# SAM3U_Breakout.net
KiCad netlist of a schematic drawn in EAGLE
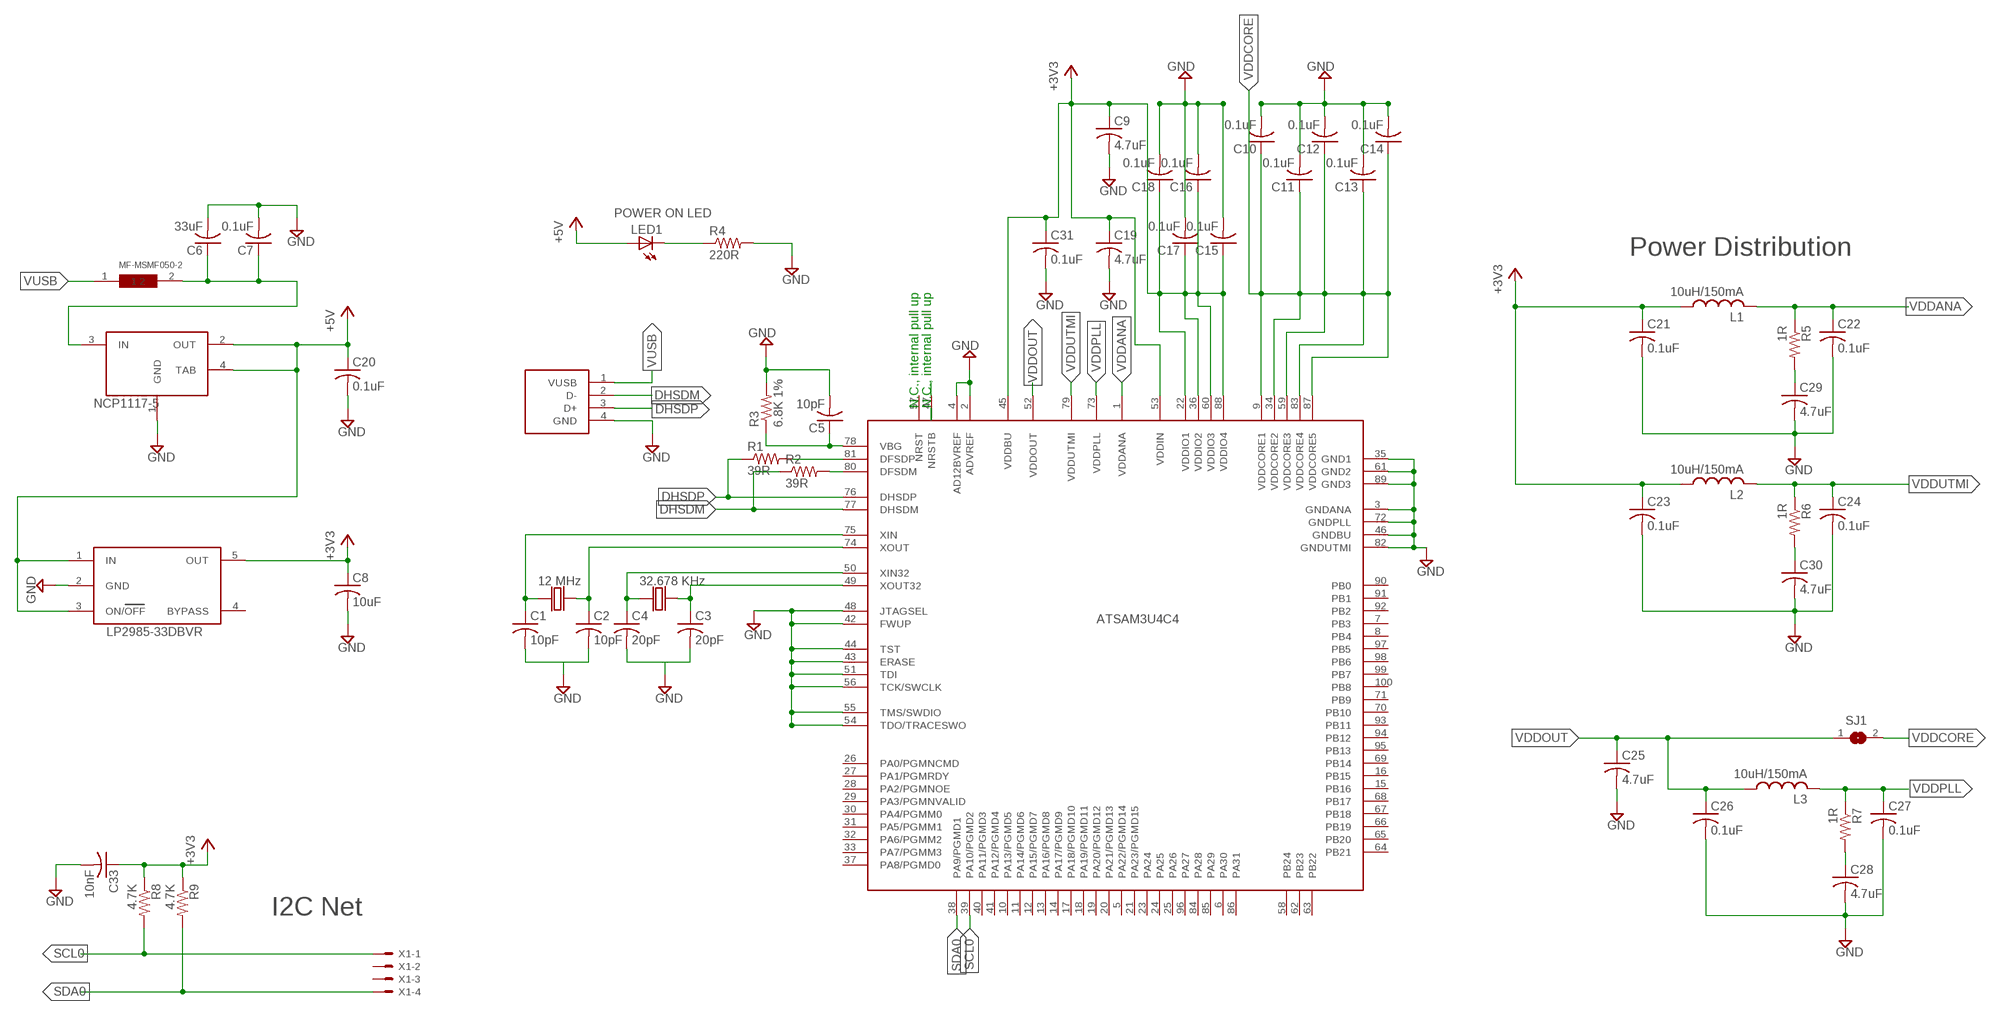
[diagram p0: schematic, sheet 1]

(export (version "E")
  (design (tool "Eeschema 10.0.6"))
  (components
    (comp (ref "C1")
      (value "10pF")
      (footprint "eagle-import:C0402K")
      (libsource (lib "eagle-import") (part "C-USC0402K"))
    )
    (comp (ref "C2")
      (value "10pF")
      (footprint "eagle-import:C0402K")
      (libsource (lib "eagle-import") (part "C-USC0402K"))
    )
    (comp (ref "C3")
      (value "20pF")
      (footprint "eagle-import:C0402K")
      (libsource (lib "eagle-import") (part "C-USC0402K"))
    )
    (comp (ref "C4")
      (value "20pF")
      (footprint "eagle-import:C0402K")
      (libsource (lib "eagle-import") (part "C-USC0402K"))
    )
    (comp (ref "C5")
      (value "10pF")
      (footprint "eagle-import:C0402K")
      (libsource (lib "eagle-import") (part "C-USC0402K"))
    )
    (comp (ref "C6")
      (value "33uF")
      (footprint "eagle-import:C0402K")
      (libsource (lib "eagle-import") (part "C-USC0402K"))
    )
    (comp (ref "C7")
      (value "0.1uF")
      (footprint "eagle-import:C0402K")
      (libsource (lib "eagle-import") (part "C-USC0402K"))
    )
    (comp (ref "C8")
      (value "10uF")
      (footprint "eagle-import:C0402K")
      (libsource (lib "eagle-import") (part "C-USC0402K"))
    )
    (comp (ref "C9")
      (value "4.7uF")
      (footprint "eagle-import:C0402K")
      (libsource (lib "eagle-import") (part "C-USC0402K"))
    )
    (comp (ref "C10")
      (value "0.1uF")
      (footprint "eagle-import:C0402K")
      (libsource (lib "eagle-import") (part "C-USC0402K"))
    )
    (comp (ref "C11")
      (value "0.1uF")
      (footprint "eagle-import:C0402K")
      (libsource (lib "eagle-import") (part "C-USC0402K"))
    )
    (comp (ref "C12")
      (value "0.1uF")
      (footprint "eagle-import:C0402K")
      (libsource (lib "eagle-import") (part "C-USC0402K"))
    )
    (comp (ref "C13")
      (value "0.1uF")
      (footprint "eagle-import:C0402K")
      (libsource (lib "eagle-import") (part "C-USC0402K"))
    )
    (comp (ref "C14")
      (value "0.1uF")
      (footprint "eagle-import:C0402K")
      (libsource (lib "eagle-import") (part "C-USC0402K"))
    )
    (comp (ref "C15")
      (value "0.1uF")
      (footprint "eagle-import:C0402K")
      (libsource (lib "eagle-import") (part "C-USC0402K"))
    )
    (comp (ref "C16")
      (value "0.1uF")
      (footprint "eagle-import:C0402K")
      (libsource (lib "eagle-import") (part "C-USC0402K"))
    )
    (comp (ref "C17")
      (value "0.1uF")
      (footprint "eagle-import:C0402K")
      (libsource (lib "eagle-import") (part "C-USC0402K"))
    )
    (comp (ref "C18")
      (value "0.1uF")
      (footprint "eagle-import:C0402K")
      (libsource (lib "eagle-import") (part "C-USC0402K"))
    )
    (comp (ref "C19")
      (value "4.7uF")
      (footprint "eagle-import:C0402K")
      (libsource (lib "eagle-import") (part "C-USC0402K"))
    )
    (comp (ref "C20")
      (value "0.1uF")
      (footprint "eagle-import:C0402K")
      (libsource (lib "eagle-import") (part "C-USC0402K"))
    )
    (comp (ref "C21")
      (value "0.1uF")
      (footprint "eagle-import:C0402K")
      (libsource (lib "eagle-import") (part "C-USC0402K"))
    )
    (comp (ref "C22")
      (value "0.1uF")
      (footprint "eagle-import:C0402K")
      (libsource (lib "eagle-import") (part "C-USC0402K"))
    )
    (comp (ref "C23")
      (value "0.1uF")
      (footprint "eagle-import:C0402K")
      (libsource (lib "eagle-import") (part "C-USC0402K"))
    )
    (comp (ref "C24")
      (value "0.1uF")
      (footprint "eagle-import:C0402K")
      (libsource (lib "eagle-import") (part "C-USC0402K"))
    )
    (comp (ref "C25")
      (value "4.7uF")
      (footprint "eagle-import:C0402K")
      (libsource (lib "eagle-import") (part "C-USC0402K"))
    )
    (comp (ref "C26")
      (value "0.1uF")
      (footprint "eagle-import:C0402K")
      (libsource (lib "eagle-import") (part "C-USC0402K"))
    )
    (comp (ref "C27")
      (value "0.1uF")
      (footprint "eagle-import:C0402K")
      (libsource (lib "eagle-import") (part "C-USC0402K"))
    )
    (comp (ref "C28")
      (value "4.7uF")
      (footprint "eagle-import:C0402K")
      (libsource (lib "eagle-import") (part "C-USC0402K"))
    )
    (comp (ref "C29")
      (value "4.7uF")
      (footprint "eagle-import:C0402K")
      (libsource (lib "eagle-import") (part "C-USC0402K"))
    )
    (comp (ref "C30")
      (value "4.7uF")
      (footprint "eagle-import:C0402K")
      (libsource (lib "eagle-import") (part "C-USC0402K"))
    )
    (comp (ref "C31")
      (value "0.1uF")
      (footprint "eagle-import:C0402K")
      (libsource (lib "eagle-import") (part "C-USC0402K"))
    )
    (comp (ref "C33")
      (value "10nF")
      (footprint "eagle-import:C0402K")
      (libsource (lib "eagle-import") (part "C-USC0402K"))
    )
    (comp (ref "L1")
      (value "10uH/150mA")
      (footprint "eagle-import:L2012C")
      (libsource (lib "eagle-import") (part "L-USL2012C"))
    )
    (comp (ref "L2")
      (value "10uH/150mA")
      (footprint "eagle-import:L2012C")
      (libsource (lib "eagle-import") (part "L-USL2012C"))
    )
    (comp (ref "L3")
      (value "10uH/150mA")
      (footprint "eagle-import:L2012C")
      (libsource (lib "eagle-import") (part "L-USL2012C"))
    )
    (comp (ref "LED1")
      (value "LEDCHIP-LED0603")
      (footprint "eagle-import:CHIP-LED0603")
      (libsource (lib "eagle-import") (part "LEDCHIP-LED0603"))
    )
    (comp (ref "R1")
      (value "39R")
      (footprint "eagle-import:R0402")
      (libsource (lib "eagle-import") (part "R-US_R0402"))
    )
    (comp (ref "R2")
      (value "39R")
      (footprint "eagle-import:R0402")
      (libsource (lib "eagle-import") (part "R-US_R0402"))
    )
    (comp (ref "R3")
      (value "6.8K 1%")
      (footprint "eagle-import:R0402")
      (libsource (lib "eagle-import") (part "resistor_R-US_R0402"))
    )
    (comp (ref "R4")
      (value "220R")
      (footprint "eagle-import:R0402")
      (libsource (lib "eagle-import") (part "R-US_R0402"))
    )
    (comp (ref "R5")
      (value "1R")
      (footprint "eagle-import:R0402")
      (libsource (lib "eagle-import") (part "resistor_R-US_R0402"))
    )
    (comp (ref "R6")
      (value "1R")
      (footprint "eagle-import:R0402")
      (libsource (lib "eagle-import") (part "resistor_R-US_R0402"))
    )
    (comp (ref "R7")
      (value "1R")
      (footprint "eagle-import:R0402")
      (libsource (lib "eagle-import") (part "resistor_R-US_R0402"))
    )
    (comp (ref "R8")
      (value "4.7K")
      (footprint "eagle-import:R0402")
      (libsource (lib "eagle-import") (part "R-US_R0402"))
    )
    (comp (ref "R9")
      (value "4.7K")
      (footprint "eagle-import:R0402")
      (libsource (lib "eagle-import") (part "R-US_R0402"))
    )
    (comp (ref "SJ1") (value "SJ") (footprint "eagle-import:SJ") (libsource (lib "eagle-import") (part "SJ")))
    (comp (ref "U$1")
      (value "ATSAM3UC4-PA")
      (footprint "eagle-import:QFP50P1600X1600X160-100N")
      (libsource (lib "eagle-import") (part "ATSAM3UC4-PA"))
    )
    (comp (ref "U$2")
      (value "USB_TYPE_A_KEYSTN")
      (footprint "eagle-import:USB_TYPE_PLUG_KSTN_PACK")
      (libsource (lib "eagle-import") (part "USB_TYPE_A_KEYSTN"))
    )
    (comp (ref "U$3")
      (value "AVX_CRYSTAL_12MHZ")
      (footprint "eagle-import:AVX_CRYSTAL_12MHZ_PACK")
      (libsource (lib "eagle-import") (part "AVX_CRYSTAL_12MHZ"))
    )
    (comp (ref "U$4")
      (value "AVX_ST43_CRYSTAL_32768")
      (footprint "eagle-import:AVX_ST32_CRYSTAL_32768_PACK")
      (libsource (lib "eagle-import") (part "AVX_ST43_CRYSTAL_32768"))
    )
    (comp (ref "U$5")
      (value "NCP1117-55V")
      (footprint "eagle-import:NCP1117-5-SOT")
      (libsource (lib "eagle-import") (part "NCP1117-55V"))
    )
    (comp (ref "U$6")
      (value "MF-MSMF050-2")
      (footprint "eagle-import:MF-MSMF050-PACK")
      (libsource (lib "eagle-import") (part "MF-MSMF050-2"))
    )
    (comp (ref "U$7")
      (value "LP2985-33DBVR5-PIN")
      (footprint "eagle-import:LP2985-33DBVR-SO")
      (libsource (lib "eagle-import") (part "LP2985-33DBVR5-PIN"))
    )
    (comp (ref "X1")
      (value "KK-156-4")
      (footprint "eagle-import:KK-156-4")
      (libsource (lib "eagle-import") (part "KK-156-4"))
    )
  )
  (nets
    (net (code "1") (name "+3V3") (class "Default")
      (node (ref "C15") (pin "1") (pinfunction "1_1") (pintype "passive"))
      (node (ref "C16") (pin "1") (pinfunction "1_1") (pintype "passive"))
      (node (ref "C17") (pin "1") (pinfunction "1_1") (pintype "passive"))
      (node (ref "C18") (pin "1") (pinfunction "1_1") (pintype "passive"))
      (node (ref "C19") (pin "1") (pinfunction "1_1") (pintype "passive"))
      (node (ref "C21") (pin "1") (pinfunction "1_1") (pintype "passive"))
      (node (ref "C23") (pin "1") (pinfunction "1_1") (pintype "passive"))
      (node (ref "C31") (pin "1") (pinfunction "1_1") (pintype "passive"))
      (node (ref "C33") (pin "1") (pinfunction "1_1") (pintype "passive"))
      (node (ref "C8") (pin "1") (pinfunction "1_1") (pintype "passive"))
      (node (ref "C9") (pin "1") (pinfunction "1_1") (pintype "passive"))
      (node (ref "L1") (pin "1") (pinfunction "1_1") (pintype "passive"))
      (node (ref "L2") (pin "1") (pinfunction "1_1") (pintype "passive"))
      (node (ref "R8") (pin "1") (pinfunction "1_1") (pintype "passive"))
      (node (ref "R9") (pin "1") (pinfunction "1_1") (pintype "passive"))
      (node (ref "U$1") (pin "22") (pinfunction "VDDIO1_22") (pintype "bidirectional"))
      (node (ref "U$1") (pin "36") (pinfunction "VDDIO2_36") (pintype "bidirectional"))
      (node (ref "U$1") (pin "45") (pinfunction "VDDBU_45") (pintype "bidirectional"))
      (node (ref "U$1") (pin "53") (pinfunction "VDDIN_53") (pintype "bidirectional"))
      (node (ref "U$1") (pin "60") (pinfunction "VDDIO3_60") (pintype "bidirectional"))
      (node (ref "U$1") (pin "88") (pinfunction "VDDIO4_88") (pintype "bidirectional"))
      (node (ref "U$7") (pin "5") (pinfunction "OUT_5") (pintype "bidirectional"))
    )
    (net (code "2") (name "+5V") (class "Default")
      (node (ref "C20") (pin "1") (pinfunction "1_1") (pintype "passive"))
      (node (ref "LED1") (pin "A") (pinfunction "A_A") (pintype "passive"))
      (node (ref "U$5") (pin "2") (pinfunction "OUT_2") (pintype "bidirectional"))
      (node (ref "U$5") (pin "4") (pinfunction "TAB_4") (pintype "bidirectional"))
      (node (ref "U$7") (pin "1") (pinfunction "IN_1") (pintype "bidirectional"))
      (node (ref "U$7") (pin "3") (pinfunction "ON/OFF_3") (pintype "bidirectional"))
    )
    (net (code "3") (name "DHSDM") (class "Default")
      (node (ref "R2") (pin "1") (pinfunction "1_1") (pintype "passive"))
      (node (ref "U$1") (pin "77") (pinfunction "DHSDM_77") (pintype "bidirectional"))
      (node (ref "U$2") (pin "2") (pinfunction "D-_2") (pintype "bidirectional"))
    )
    (net (code "4") (name "DHSDP") (class "Default")
      (node (ref "R1") (pin "1") (pinfunction "1_1") (pintype "passive"))
      (node (ref "U$1") (pin "76") (pinfunction "DHSDP_76") (pintype "bidirectional"))
      (node (ref "U$2") (pin "3") (pinfunction "D+_3") (pintype "bidirectional"))
    )
    (net (code "5") (name "GND") (class "Default")
      (node (ref "C1") (pin "2") (pinfunction "2_2") (pintype "passive"))
      (node (ref "C10") (pin "2") (pinfunction "2_2") (pintype "passive"))
      (node (ref "C11") (pin "2") (pinfunction "2_2") (pintype "passive"))
      (node (ref "C12") (pin "2") (pinfunction "2_2") (pintype "passive"))
      (node (ref "C13") (pin "2") (pinfunction "2_2") (pintype "passive"))
      (node (ref "C14") (pin "2") (pinfunction "2_2") (pintype "passive"))
      (node (ref "C15") (pin "2") (pinfunction "2_2") (pintype "passive"))
      (node (ref "C16") (pin "2") (pinfunction "2_2") (pintype "passive"))
      (node (ref "C17") (pin "2") (pinfunction "2_2") (pintype "passive"))
      (node (ref "C18") (pin "2") (pinfunction "2_2") (pintype "passive"))
      (node (ref "C19") (pin "2") (pinfunction "2_2") (pintype "passive"))
      (node (ref "C2") (pin "2") (pinfunction "2_2") (pintype "passive"))
      (node (ref "C20") (pin "2") (pinfunction "2_2") (pintype "passive"))
      (node (ref "C21") (pin "2") (pinfunction "2_2") (pintype "passive"))
      (node (ref "C22") (pin "2") (pinfunction "2_2") (pintype "passive"))
      (node (ref "C23") (pin "2") (pinfunction "2_2") (pintype "passive"))
      (node (ref "C24") (pin "2") (pinfunction "2_2") (pintype "passive"))
      (node (ref "C25") (pin "2") (pinfunction "2_2") (pintype "passive"))
      (node (ref "C26") (pin "2") (pinfunction "2_2") (pintype "passive"))
      (node (ref "C27") (pin "2") (pinfunction "2_2") (pintype "passive"))
      (node (ref "C28") (pin "2") (pinfunction "2_2") (pintype "passive"))
      (node (ref "C29") (pin "2") (pinfunction "2_2") (pintype "passive"))
      (node (ref "C3") (pin "2") (pinfunction "2_2") (pintype "passive"))
      (node (ref "C30") (pin "2") (pinfunction "2_2") (pintype "passive"))
      (node (ref "C31") (pin "2") (pinfunction "2_2") (pintype "passive"))
      (node (ref "C33") (pin "2") (pinfunction "2_2") (pintype "passive"))
      (node (ref "C4") (pin "2") (pinfunction "2_2") (pintype "passive"))
      (node (ref "C5") (pin "2") (pinfunction "2_2") (pintype "passive"))
      (node (ref "C6") (pin "2") (pinfunction "2_2") (pintype "passive"))
      (node (ref "C7") (pin "2") (pinfunction "2_2") (pintype "passive"))
      (node (ref "C8") (pin "2") (pinfunction "2_2") (pintype "passive"))
      (node (ref "C9") (pin "2") (pinfunction "2_2") (pintype "passive"))
      (node (ref "R3") (pin "2") (pinfunction "2_2") (pintype "passive"))
      (node (ref "R4") (pin "2") (pinfunction "2_2") (pintype "passive"))
      (node (ref "U$1") (pin "2") (pinfunction "ADVREF_2") (pintype "bidirectional"))
      (node (ref "U$1") (pin "3") (pinfunction "GNDANA_3") (pintype "bidirectional"))
      (node (ref "U$1") (pin "35") (pinfunction "GND1_35") (pintype "bidirectional"))
      (node (ref "U$1") (pin "4") (pinfunction "AD12BVREF_4") (pintype "bidirectional"))
      (node (ref "U$1") (pin "42") (pinfunction "FWUP_42") (pintype "bidirectional"))
      (node (ref "U$1") (pin "43") (pinfunction "ERASE_43") (pintype "bidirectional"))
      (node (ref "U$1") (pin "44") (pinfunction "TST_44") (pintype "bidirectional"))
      (node (ref "U$1") (pin "46") (pinfunction "GNDBU_46") (pintype "bidirectional"))
      (node (ref "U$1") (pin "48") (pinfunction "JTAGSEL_48") (pintype "bidirectional"))
      (node (ref "U$1") (pin "51") (pinfunction "TDI_51") (pintype "bidirectional"))
      (node (ref "U$1") (pin "54") (pinfunction "TDO/TRACESWO_54") (pintype "bidirectional"))
      (node (ref "U$1") (pin "55") (pinfunction "TMS/SWDIO_55") (pintype "bidirectional"))
      (node (ref "U$1") (pin "56") (pinfunction "TCK/SWCLK_56") (pintype "bidirectional"))
      (node (ref "U$1") (pin "61") (pinfunction "GND2_61") (pintype "bidirectional"))
      (node (ref "U$1") (pin "72") (pinfunction "GNDPLL_72") (pintype "bidirectional"))
      (node (ref "U$1") (pin "82") (pinfunction "GNDUTMI_82") (pintype "bidirectional"))
      (node (ref "U$1") (pin "89") (pinfunction "GND3_89") (pintype "bidirectional"))
      (node (ref "U$2") (pin "4") (pinfunction "GND_4") (pintype "bidirectional"))
      (node (ref "U$5") (pin "1") (pinfunction "GND_1") (pintype "bidirectional"))
      (node (ref "U$7") (pin "2") (pinfunction "GND_2") (pintype "bidirectional"))
    )
    (net (code "6") (name "Net-(C28-Pad1)") (class "Default")
      (node (ref "C28") (pin "1") (pinfunction "1_1") (pintype "passive"))
      (node (ref "R7") (pin "2") (pinfunction "2_2") (pintype "passive"))
    )
    (net (code "7") (name "Net-(C29-Pad1)") (class "Default")
      (node (ref "C29") (pin "1") (pinfunction "1_1") (pintype "passive"))
      (node (ref "R5") (pin "2") (pinfunction "2_2") (pintype "passive"))
    )
    (net (code "8") (name "Net-(C30-Pad1)") (class "Default")
      (node (ref "C30") (pin "1") (pinfunction "1_1") (pintype "passive"))
      (node (ref "R6") (pin "2") (pinfunction "2_2") (pintype "passive"))
    )
    (net (code "9") (name "Net-(LED1-PadC)") (class "Default")
      (node (ref "LED1") (pin "C") (pinfunction "C_C") (pintype "passive"))
      (node (ref "R4") (pin "1") (pinfunction "1_1") (pintype "passive"))
    )
    (net (code "10") (name "Net-(U$1-DFSDM)") (class "Default")
      (node (ref "R2") (pin "2") (pinfunction "2_2") (pintype "passive"))
      (node (ref "U$1") (pin "80") (pinfunction "DFSDM_80") (pintype "bidirectional"))
    )
    (net (code "11") (name "Net-(U$1-DFSDP)") (class "Default")
      (node (ref "R1") (pin "2") (pinfunction "2_2") (pintype "passive"))
      (node (ref "U$1") (pin "81") (pinfunction "DFSDP_81") (pintype "bidirectional"))
    )
    (net (code "12") (name "Net-(U$1-VBG)") (class "Default")
      (node (ref "C5") (pin "1") (pinfunction "1_1") (pintype "passive"))
      (node (ref "R3") (pin "1") (pinfunction "1_1") (pintype "passive"))
      (node (ref "U$1") (pin "78") (pinfunction "VBG_78") (pintype "bidirectional"))
    )
    (net (code "13") (name "Net-(U$1-XIN)") (class "Default")
      (node (ref "C1") (pin "1") (pinfunction "1_1") (pintype "passive"))
      (node (ref "U$1") (pin "75") (pinfunction "XIN_75") (pintype "bidirectional"))
      (node (ref "U$3") (pin "1") (pinfunction "P$1_1") (pintype "bidirectional"))
    )
    (net (code "14") (name "Net-(U$1-XIN32)") (class "Default")
      (node (ref "C4") (pin "1") (pinfunction "1_1") (pintype "passive"))
      (node (ref "U$1") (pin "50") (pinfunction "XIN32_50") (pintype "bidirectional"))
      (node (ref "U$4") (pin "1") (pinfunction "P$1_1") (pintype "bidirectional"))
    )
    (net (code "15") (name "Net-(U$1-XOUT)") (class "Default")
      (node (ref "C2") (pin "1") (pinfunction "1_1") (pintype "passive"))
      (node (ref "U$1") (pin "74") (pinfunction "XOUT_74") (pintype "bidirectional"))
      (node (ref "U$3") (pin "2") (pinfunction "P$2_2") (pintype "bidirectional"))
    )
    (net (code "16") (name "Net-(U$1-XOUT32)") (class "Default")
      (node (ref "C3") (pin "1") (pinfunction "1_1") (pintype "passive"))
      (node (ref "U$1") (pin "49") (pinfunction "XOUT32_49") (pintype "bidirectional"))
      (node (ref "U$4") (pin "2") (pinfunction "P$2_2") (pintype "bidirectional"))
    )
    (net (code "17") (name "Net-(U$5-IN)") (class "Default")
      (node (ref "C6") (pin "1") (pinfunction "1_1") (pintype "passive"))
      (node (ref "C7") (pin "1") (pinfunction "1_1") (pintype "passive"))
      (node (ref "U$5") (pin "3") (pinfunction "IN_3") (pintype "bidirectional"))
      (node (ref "U$6") (pin "2") (pinfunction "2_2") (pintype "bidirectional"))
    )
    (net (code "18") (name "SCL0") (class "Default")
      (node (ref "R8") (pin "2") (pinfunction "2_2") (pintype "passive"))
      (node (ref "U$1") (pin "39") (pinfunction "PA10/PGMD2_39") (pintype "bidirectional"))
      (node (ref "X1") (pin "1") (pinfunction "S_1") (pintype "passive"))
    )
    (net (code "19") (name "SDA0") (class "Default")
      (node (ref "R9") (pin "2") (pinfunction "2_2") (pintype "passive"))
      (node (ref "U$1") (pin "38") (pinfunction "PA9/PGMD1_38") (pintype "bidirectional"))
      (node (ref "X1") (pin "4") (pinfunction "S_4") (pintype "passive"))
    )
    (net (code "20") (name "VDDANA") (class "Default")
      (node (ref "C22") (pin "1") (pinfunction "1_1") (pintype "passive"))
      (node (ref "L1") (pin "2") (pinfunction "2_2") (pintype "passive"))
      (node (ref "R5") (pin "1") (pinfunction "1_1") (pintype "passive"))
      (node (ref "U$1") (pin "1") (pinfunction "VDDANA_1") (pintype "bidirectional"))
    )
    (net (code "21") (name "VDDCORE") (class "Default")
      (node (ref "C10") (pin "1") (pinfunction "1_1") (pintype "passive"))
      (node (ref "C11") (pin "1") (pinfunction "1_1") (pintype "passive"))
      (node (ref "C12") (pin "1") (pinfunction "1_1") (pintype "passive"))
      (node (ref "C13") (pin "1") (pinfunction "1_1") (pintype "passive"))
      (node (ref "C14") (pin "1") (pinfunction "1_1") (pintype "passive"))
      (node (ref "SJ1") (pin "2") (pinfunction "2_2") (pintype "passive"))
      (node (ref "U$1") (pin "34") (pinfunction "VDDCORE2_34") (pintype "bidirectional"))
      (node (ref "U$1") (pin "59") (pinfunction "VDDCORE3_59") (pintype "bidirectional"))
      (node (ref "U$1") (pin "83") (pinfunction "VDDCORE4_83") (pintype "bidirectional"))
      (node (ref "U$1") (pin "87") (pinfunction "VDDCORE5_87") (pintype "bidirectional"))
      (node (ref "U$1") (pin "9") (pinfunction "VDDCORE1_9") (pintype "bidirectional"))
    )
    (net (code "22") (name "VDDOUT") (class "Default")
      (node (ref "C25") (pin "1") (pinfunction "1_1") (pintype "passive"))
      (node (ref "C26") (pin "1") (pinfunction "1_1") (pintype "passive"))
      (node (ref "L3") (pin "1") (pinfunction "1_1") (pintype "passive"))
      (node (ref "SJ1") (pin "1") (pinfunction "1_1") (pintype "passive"))
      (node (ref "U$1") (pin "52") (pinfunction "VDDOUT_52") (pintype "bidirectional"))
    )
    (net (code "23") (name "VDDPLL") (class "Default")
      (node (ref "C27") (pin "1") (pinfunction "1_1") (pintype "passive"))
      (node (ref "L3") (pin "2") (pinfunction "2_2") (pintype "passive"))
      (node (ref "R7") (pin "1") (pinfunction "1_1") (pintype "passive"))
      (node (ref "U$1") (pin "73") (pinfunction "VDDPLL_73") (pintype "bidirectional"))
    )
    (net (code "24") (name "VDDUTMI") (class "Default")
      (node (ref "C24") (pin "1") (pinfunction "1_1") (pintype "passive"))
      (node (ref "L2") (pin "2") (pinfunction "2_2") (pintype "passive"))
      (node (ref "R6") (pin "1") (pinfunction "1_1") (pintype "passive"))
      (node (ref "U$1") (pin "79") (pinfunction "VDDUTMI_79") (pintype "bidirectional"))
    )
    (net (code "25") (name "VUSB") (class "Default")
      (node (ref "U$2") (pin "1") (pinfunction "VUSB_1") (pintype "bidirectional"))
      (node (ref "U$6") (pin "1") (pinfunction "1_1") (pintype "bidirectional"))
    )
    (net (code "26") (name "unconnected-(U$1-NRST-Pad57)") (class "Default")
      (node (ref "U$1") (pin "57") (pinfunction "NRST_57") (pintype "bidirectional"))
    )
    (net (code "27") (name "unconnected-(U$1-NRSTB-Pad47)") (class "Default")
      (node (ref "U$1") (pin "47") (pinfunction "NRSTB_47") (pintype "bidirectional"))
    )
    (net (code "28") (name "unconnected-(U$1-PA0{slash}PGMNCMD-Pad26)") (class "Default")
      (node (ref "U$1") (pin "26") (pinfunction "PA0/PGMNCMD_26") (pintype "bidirectional"))
    )
    (net (code "29") (name "unconnected-(U$1-PA1{slash}PGMRDY-Pad27)") (class "Default")
      (node (ref "U$1") (pin "27") (pinfunction "PA1/PGMRDY_27") (pintype "bidirectional"))
    )
    (net (code "30") (name "unconnected-(U$1-PA2{slash}PGMNOE-Pad28)") (class "Default")
      (node (ref "U$1") (pin "28") (pinfunction "PA2/PGMNOE_28") (pintype "bidirectional"))
    )
    (net (code "31") (name "unconnected-(U$1-PA3{slash}PGMNVALID-Pad29)") (class "Default")
      (node (ref "U$1") (pin "29") (pinfunction "PA3/PGMNVALID_29") (pintype "bidirectional"))
    )
    (net (code "32") (name "unconnected-(U$1-PA4{slash}PGMM0-Pad30)") (class "Default")
      (node (ref "U$1") (pin "30") (pinfunction "PA4/PGMM0_30") (pintype "bidirectional"))
    )
    (net (code "33") (name "unconnected-(U$1-PA5{slash}PGMM1-Pad31)") (class "Default")
      (node (ref "U$1") (pin "31") (pinfunction "PA5/PGMM1_31") (pintype "bidirectional"))
    )
    (net (code "34") (name "unconnected-(U$1-PA6{slash}PGMM2-Pad32)") (class "Default")
      (node (ref "U$1") (pin "32") (pinfunction "PA6/PGMM2_32") (pintype "bidirectional"))
    )
    (net (code "35") (name "unconnected-(U$1-PA7{slash}PGMM3-Pad33)") (class "Default")
      (node (ref "U$1") (pin "33") (pinfunction "PA7/PGMM3_33") (pintype "bidirectional"))
    )
    (net (code "36") (name "unconnected-(U$1-PA8{slash}PGMD0-Pad37)") (class "Default")
      (node (ref "U$1") (pin "37") (pinfunction "PA8/PGMD0_37") (pintype "bidirectional"))
    )
    (net (code "37") (name "unconnected-(U$1-PA11{slash}PGMD3-Pad40)") (class "Default")
      (node (ref "U$1") (pin "40") (pinfunction "PA11/PGMD3_40") (pintype "bidirectional"))
    )
    (net (code "38") (name "unconnected-(U$1-PA12{slash}PGMD4-Pad41)") (class "Default")
      (node (ref "U$1") (pin "41") (pinfunction "PA12/PGMD4_41") (pintype "bidirectional"))
    )
    (net (code "39") (name "unconnected-(U$1-PA13{slash}PGMD5-Pad10)") (class "Default")
      (node (ref "U$1") (pin "10") (pinfunction "PA13/PGMD5_10") (pintype "bidirectional"))
    )
    (net (code "40") (name "unconnected-(U$1-PA14{slash}PGMD6-Pad11)") (class "Default")
      (node (ref "U$1") (pin "11") (pinfunction "PA14/PGMD6_11") (pintype "bidirectional"))
    )
    (net (code "41") (name "unconnected-(U$1-PA15{slash}PGMD7-Pad12)") (class "Default")
      (node (ref "U$1") (pin "12") (pinfunction "PA15/PGMD7_12") (pintype "bidirectional"))
    )
    (net (code "42") (name "unconnected-(U$1-PA16{slash}PGMD8-Pad13)") (class "Default")
      (node (ref "U$1") (pin "13") (pinfunction "PA16/PGMD8_13") (pintype "bidirectional"))
    )
    (net (code "43") (name "unconnected-(U$1-PA17{slash}PGMD9-Pad14)") (class "Default")
      (node (ref "U$1") (pin "14") (pinfunction "PA17/PGMD9_14") (pintype "bidirectional"))
    )
    (net (code "44") (name "unconnected-(U$1-PA18{slash}PGMD10-Pad17)") (class "Default")
      (node (ref "U$1") (pin "17") (pinfunction "PA18/PGMD10_17") (pintype "bidirectional"))
    )
    (net (code "45") (name "unconnected-(U$1-PA19{slash}PGMD11-Pad18)") (class "Default")
      (node (ref "U$1") (pin "18") (pinfunction "PA19/PGMD11_18") (pintype "bidirectional"))
    )
    (net (code "46") (name "unconnected-(U$1-PA20{slash}PGMD12-Pad19)") (class "Default")
      (node (ref "U$1") (pin "19") (pinfunction "PA20/PGMD12_19") (pintype "bidirectional"))
    )
    (net (code "47") (name "unconnected-(U$1-PA21{slash}PGMD13-Pad20)") (class "Default")
      (node (ref "U$1") (pin "20") (pinfunction "PA21/PGMD13_20") (pintype "bidirectional"))
    )
    (net (code "48") (name "unconnected-(U$1-PA22{slash}PGMD14-Pad5)") (class "Default")
      (node (ref "U$1") (pin "5") (pinfunction "PA22/PGMD14_5") (pintype "bidirectional"))
    )
    (net (code "49") (name "unconnected-(U$1-PA23{slash}PGMD15-Pad21)") (class "Default")
      (node (ref "U$1") (pin "21") (pinfunction "PA23/PGMD15_21") (pintype "bidirectional"))
    )
    (net (code "50") (name "unconnected-(U$1-PA24-Pad23)") (class "Default")
      (node (ref "U$1") (pin "23") (pinfunction "PA24_23") (pintype "bidirectional"))
    )
    (net (code "51") (name "unconnected-(U$1-PA25-Pad24)") (class "Default")
      (node (ref "U$1") (pin "24") (pinfunction "PA25_24") (pintype "bidirectional"))
    )
    (net (code "52") (name "unconnected-(U$1-PA26-Pad25)") (class "Default")
      (node (ref "U$1") (pin "25") (pinfunction "PA26_25") (pintype "bidirectional"))
    )
    (net (code "53") (name "unconnected-(U$1-PA27-Pad96)") (class "Default")
      (node (ref "U$1") (pin "96") (pinfunction "PA27_96") (pintype "bidirectional"))
    )
    (net (code "54") (name "unconnected-(U$1-PA28-Pad84)") (class "Default")
      (node (ref "U$1") (pin "84") (pinfunction "PA28_84") (pintype "bidirectional"))
    )
    (net (code "55") (name "unconnected-(U$1-PA29-Pad85)") (class "Default")
      (node (ref "U$1") (pin "85") (pinfunction "PA29_85") (pintype "bidirectional"))
    )
    (net (code "56") (name "unconnected-(U$1-PA30-Pad6)") (class "Default")
      (node (ref "U$1") (pin "6") (pinfunction "PA30_6") (pintype "bidirectional"))
    )
    (net (code "57") (name "unconnected-(U$1-PA31-Pad86)") (class "Default")
      (node (ref "U$1") (pin "86") (pinfunction "PA31_86") (pintype "bidirectional"))
    )
    (net (code "58") (name "unconnected-(U$1-PB0-Pad90)") (class "Default")
      (node (ref "U$1") (pin "90") (pinfunction "PB0_90") (pintype "bidirectional"))
    )
    (net (code "59") (name "unconnected-(U$1-PB1-Pad91)") (class "Default")
      (node (ref "U$1") (pin "91") (pinfunction "PB1_91") (pintype "bidirectional"))
    )
    (net (code "60") (name "unconnected-(U$1-PB2-Pad92)") (class "Default")
      (node (ref "U$1") (pin "92") (pinfunction "PB2_92") (pintype "bidirectional"))
    )
    (net (code "61") (name "unconnected-(U$1-PB3-Pad7)") (class "Default")
      (node (ref "U$1") (pin "7") (pinfunction "PB3_7") (pintype "bidirectional"))
    )
    (net (code "62") (name "unconnected-(U$1-PB4-Pad8)") (class "Default")
      (node (ref "U$1") (pin "8") (pinfunction "PB4_8") (pintype "bidirectional"))
    )
    (net (code "63") (name "unconnected-(U$1-PB5-Pad97)") (class "Default")
      (node (ref "U$1") (pin "97") (pinfunction "PB5_97") (pintype "bidirectional"))
    )
    (net (code "64") (name "unconnected-(U$1-PB6-Pad98)") (class "Default")
      (node (ref "U$1") (pin "98") (pinfunction "PB6_98") (pintype "bidirectional"))
    )
    (net (code "65") (name "unconnected-(U$1-PB7-Pad99)") (class "Default")
      (node (ref "U$1") (pin "99") (pinfunction "PB7_99") (pintype "bidirectional"))
    )
    (net (code "66") (name "unconnected-(U$1-PB8-Pad100)") (class "Default")
      (node (ref "U$1") (pin "100") (pinfunction "PB8_100") (pintype "bidirectional"))
    )
    (net (code "67") (name "unconnected-(U$1-PB9-Pad71)") (class "Default")
      (node (ref "U$1") (pin "71") (pinfunction "PB9_71") (pintype "bidirectional"))
    )
    (net (code "68") (name "unconnected-(U$1-PB10-Pad70)") (class "Default")
      (node (ref "U$1") (pin "70") (pinfunction "PB10_70") (pintype "bidirectional"))
    )
    (net (code "69") (name "unconnected-(U$1-PB11-Pad93)") (class "Default")
      (node (ref "U$1") (pin "93") (pinfunction "PB11_93") (pintype "bidirectional"))
    )
    (net (code "70") (name "unconnected-(U$1-PB12-Pad94)") (class "Default")
      (node (ref "U$1") (pin "94") (pinfunction "PB12_94") (pintype "bidirectional"))
    )
    (net (code "71") (name "unconnected-(U$1-PB13-Pad95)") (class "Default")
      (node (ref "U$1") (pin "95") (pinfunction "PB13_95") (pintype "bidirectional"))
    )
    (net (code "72") (name "unconnected-(U$1-PB14-Pad69)") (class "Default")
      (node (ref "U$1") (pin "69") (pinfunction "PB14_69") (pintype "bidirectional"))
    )
    (net (code "73") (name "unconnected-(U$1-PB15-Pad16)") (class "Default")
      (node (ref "U$1") (pin "16") (pinfunction "PB15_16") (pintype "bidirectional"))
    )
    (net (code "74") (name "unconnected-(U$1-PB16-Pad15)") (class "Default")
      (node (ref "U$1") (pin "15") (pinfunction "PB16_15") (pintype "bidirectional"))
    )
    (net (code "75") (name "unconnected-(U$1-PB17-Pad68)") (class "Default")
      (node (ref "U$1") (pin "68") (pinfunction "PB17_68") (pintype "bidirectional"))
    )
    (net (code "76") (name "unconnected-(U$1-PB18-Pad67)") (class "Default")
      (node (ref "U$1") (pin "67") (pinfunction "PB18_67") (pintype "bidirectional"))
    )
    (net (code "77") (name "unconnected-(U$1-PB19-Pad66)") (class "Default")
      (node (ref "U$1") (pin "66") (pinfunction "PB19_66") (pintype "bidirectional"))
    )
    (net (code "78") (name "unconnected-(U$1-PB20-Pad65)") (class "Default")
      (node (ref "U$1") (pin "65") (pinfunction "PB20_65") (pintype "bidirectional"))
    )
    (net (code "79") (name "unconnected-(U$1-PB21-Pad64)") (class "Default")
      (node (ref "U$1") (pin "64") (pinfunction "PB21_64") (pintype "bidirectional"))
    )
    (net (code "80") (name "unconnected-(U$1-PB22-Pad63)") (class "Default")
      (node (ref "U$1") (pin "63") (pinfunction "PB22_63") (pintype "bidirectional"))
    )
    (net (code "81") (name "unconnected-(U$1-PB23-Pad62)") (class "Default")
      (node (ref "U$1") (pin "62") (pinfunction "PB23_62") (pintype "bidirectional"))
    )
    (net (code "82") (name "unconnected-(U$1-PB24-Pad58)") (class "Default")
      (node (ref "U$1") (pin "58") (pinfunction "PB24_58") (pintype "bidirectional"))
    )
    (net (code "83") (name "unconnected-(U$7-BYPASS-Pad4)") (class "Default")
      (node (ref "U$7") (pin "4") (pinfunction "BYPASS_4") (pintype "bidirectional"))
    )
    (net (code "84") (name "unconnected-(X1B-S-Pad2)") (class "Default")
      (node (ref "X1") (pin "2") (pinfunction "S_2") (pintype "passive"))
    )
    (net (code "85") (name "unconnected-(X1C-S-Pad3)") (class "Default")
      (node (ref "X1") (pin "3") (pinfunction "S_3") (pintype "passive"))
    )
  )
)
